# MJ808_clone_-_all_driver_-_prod_-_23mm.net
KiCad netlist of a schematic drawn in EAGLE
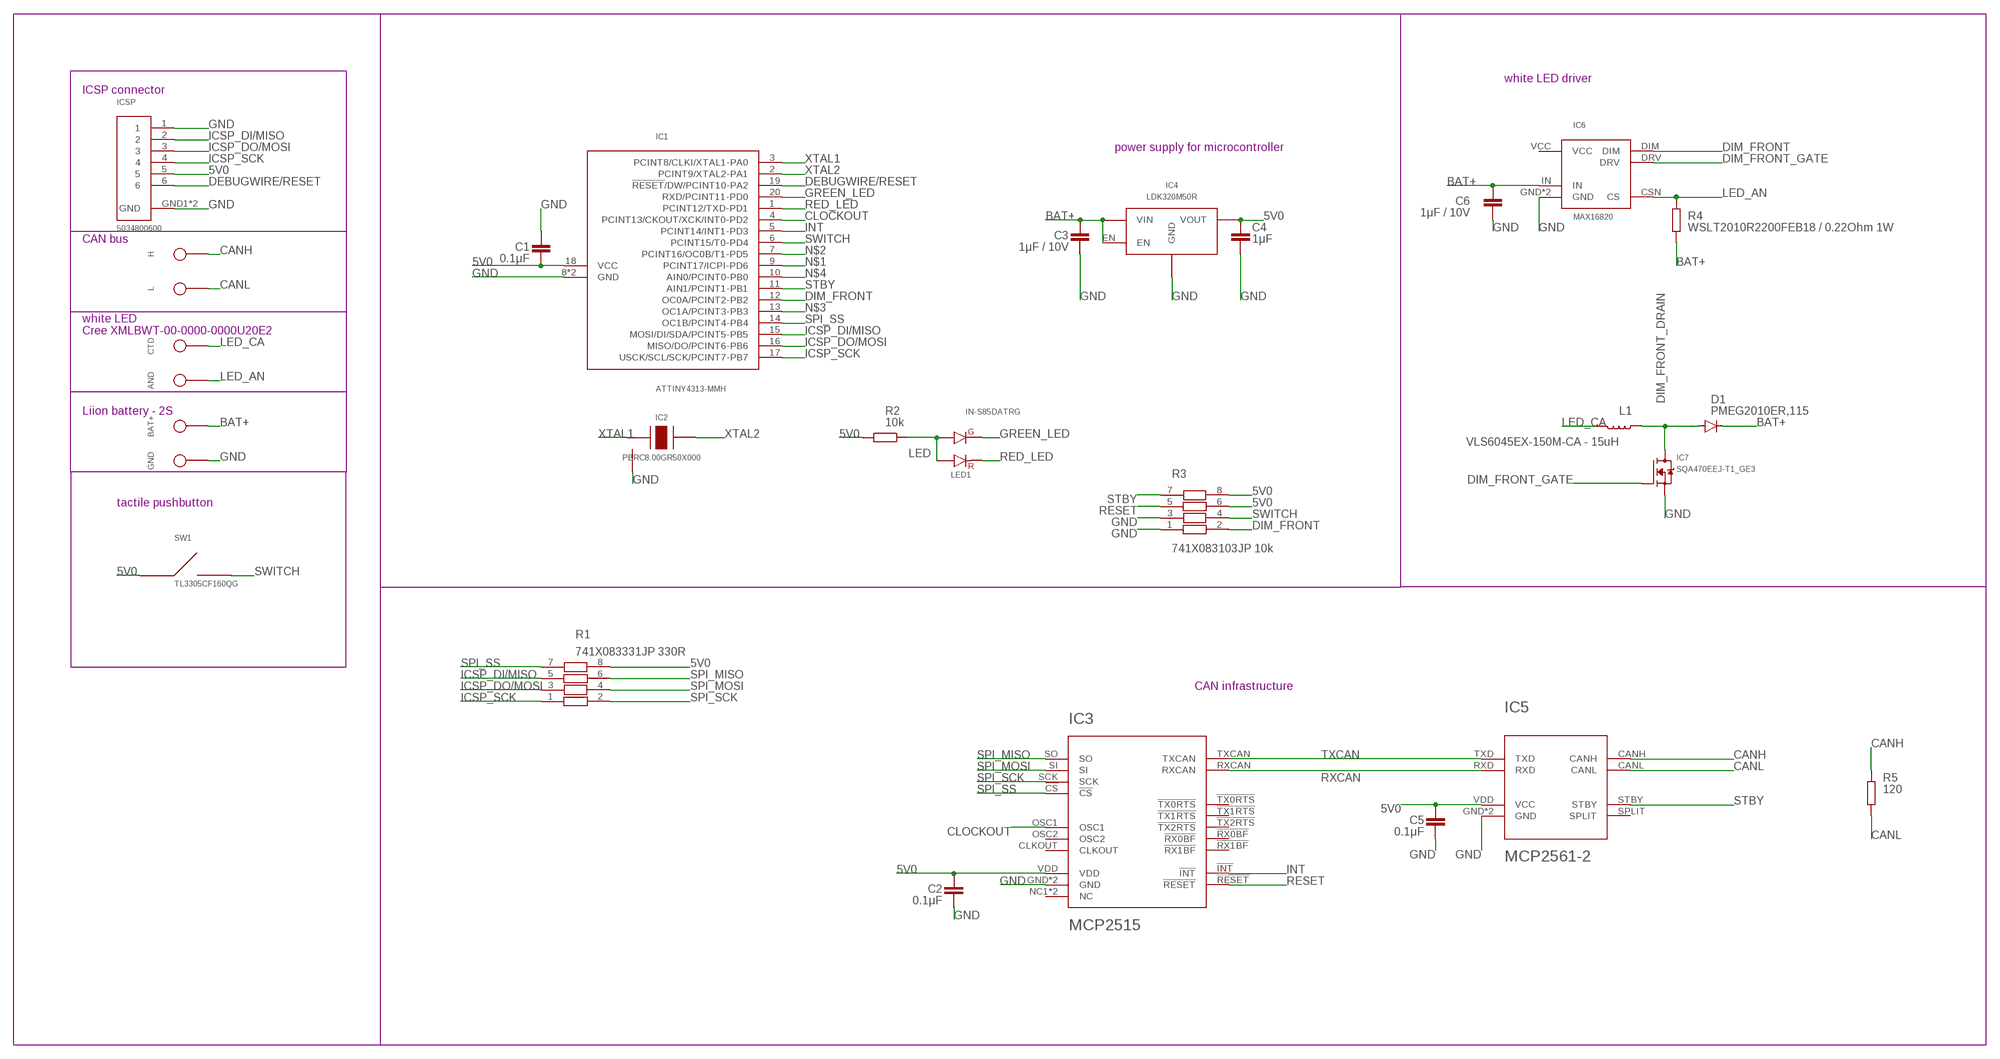
[diagram p0: schematic, sheet 1]

(export (version "E")
  (design (tool "Eeschema 10.0.6"))
  (components
    (comp (ref "AND")
      (value "LED anode")
      (footprint "eagle-import:TH-1.2MM")
      (libsource (lib "eagle-import") (part "TPTH-1.2MM"))
    )
    (comp (ref "BAT+")
      (value "LiIon + Terminal")
      (footprint "eagle-import:TH-1.2MM")
      (libsource (lib "eagle-import") (part "TPTH-1.2MM"))
    )
    (comp (ref "C1")
      (value "0.1μF")
      (footprint "eagle-import:C0402")
      (libsource (lib "eagle-import") (part "C-EUC0402"))
    )
    (comp (ref "C2")
      (value "0.1μF")
      (footprint "eagle-import:C0402")
      (libsource (lib "eagle-import") (part "C-EUC0402"))
    )
    (comp (ref "C3")
      (value "1μF / 10V")
      (footprint "eagle-import:C0402")
      (libsource (lib "eagle-import") (part "C-EUC0402"))
    )
    (comp (ref "C4")
      (value "1μF")
      (footprint "eagle-import:C0402")
      (libsource (lib "eagle-import") (part "C-EUC0402"))
    )
    (comp (ref "C5")
      (value "0.1μF")
      (footprint "eagle-import:C0402")
      (libsource (lib "eagle-import") (part "C-EUC0402"))
    )
    (comp (ref "C6")
      (value "1μF / 10V")
      (footprint "eagle-import:C0402")
      (libsource (lib "eagle-import") (part "C-EUC0402"))
    )
    (comp (ref "CTD")
      (value "LED cathode")
      (footprint "eagle-import:TH-1.2MM")
      (libsource (lib "eagle-import") (part "TPTH-1.2MM"))
    )
    (comp (ref "D1")
      (value "PMEG2010ER,115")
      (footprint "eagle-import:SOD123")
      (libsource (lib "eagle-import") (part "DIODE-SOD123"))
    )
    (comp (ref "GND")
      (value "LiIon - Terminal")
      (footprint "eagle-import:TH-1.2MM")
      (libsource (lib "eagle-import") (part "TPTH-1.2MM"))
    )
    (comp (ref "H")
      (value "CAN high")
      (footprint "eagle-import:TH-1.2MM")
      (libsource (lib "eagle-import") (part "TPTH-1.2MM"))
    )
    (comp (ref "IC1")
      (value "ATTINY4313-MMH")
      (footprint "eagle-import:VQFN-20")
      (fields (field (name "SPICEPREFIX") "X"))
      (libsource (lib "eagle-import") (part "ATTINY4313VQFN-20"))
    )
    (comp (ref "IC2")
      (value "PBRC8.00GR50X000")
      (footprint "eagle-import:SMT")
      (libsource (lib "eagle-import") (part "PRQV"))
    )
    (comp (ref "IC3")
      (value "MCP2515")
      (footprint "eagle-import:QFN20")
      (libsource (lib "eagle-import") (part "MCP2515-I-ML"))
    )
    (comp (ref "IC4")
      (value "LDK320M50R")
      (footprint "eagle-import:SOT-23-5L")
      (libsource (lib "eagle-import") (part "LDK320SOT-23-5L"))
    )
    (comp (ref "IC5")
      (value "MCP2561-2")
      (footprint "eagle-import:DFN10")
      (libsource (lib "eagle-import") (part "MCP2561-2"))
    )
    (comp (ref "IC6")
      (value "MAX16820")
      (footprint "eagle-import:TDFN-6-EP")
      (libsource (lib "eagle-import") (part "MAX16820"))
    )
    (comp (ref "IC7")
      (value "SQA470EEJ-T1_GE3")
      (footprint "eagle-import:SC-70-6")
      (libsource (lib "eagle-import") (part "SIA456DJ"))
    )
    (comp (ref "ICSP")
      (value "5034800600")
      (footprint "eagle-import:SMT")
      (libsource (lib "eagle-import") (part "5034800600"))
    )
    (comp (ref "L")
      (value "CAN low")
      (footprint "eagle-import:TH-1.2MM")
      (libsource (lib "eagle-import") (part "TPTH-1.2MM"))
    )
    (comp (ref "L1")
      (value "VLS6045EX-150M-CA - 15uH")
      (footprint "eagle-import:SRN6045")
      (libsource (lib "eagle-import") (part "INDUCTOR-SRN6045-33UH"))
    )
    (comp (ref "LED1")
      (value "IN-S85DATRG")
      (footprint "eagle-import:SMD")
      (libsource (lib "eagle-import") (part "APHBM2012LSURKZGKC"))
    )
    (comp (ref "R1")
      (value "741X083331JP 330R")
      (footprint "eagle-import:0402-4R")
      (libsource (lib "eagle-import") (part "741X083331JP"))
    )
    (comp (ref "R2")
      (value "10k")
      (footprint "eagle-import:R0402")
      (libsource (lib "eagle-import") (part "R-EU_R0402"))
    )
    (comp (ref "R3")
      (value "741X083103JP 10k")
      (footprint "eagle-import:0402-4R")
      (libsource (lib "eagle-import") (part "741X083331JP"))
    )
    (comp (ref "R4")
      (value "WSLT2010R2200FEB18 / 0.22Ohm 1W")
      (footprint "eagle-import:R2010")
      (libsource (lib "eagle-import") (part "R-EU_R2010"))
    )
    (comp (ref "R5")
      (value "120")
      (footprint "eagle-import:R0805")
      (libsource (lib "eagle-import") (part "R-EU_R0805"))
    )
    (comp (ref "SW1")
      (value "TL3305CF160QG")
      (footprint "eagle-import:SMD")
      (libsource (lib "eagle-import") (part "TL3305-844809"))
    )
  )
  (nets
    (net (code "1") (name "/5V0") (class "Default")
      (node (ref "C1") (pin "1") (pinfunction "1_1") (pintype "passive"))
      (node (ref "C2") (pin "1") (pinfunction "1_1") (pintype "passive"))
      (node (ref "C4") (pin "2") (pinfunction "2_2") (pintype "passive"))
      (node (ref "C5") (pin "1") (pinfunction "1_1") (pintype "passive"))
      (node (ref "IC1") (pin "18") (pinfunction "VCC_18") (pintype "bidirectional"))
      (node (ref "IC3") (pin "VDD") (pinfunction "VDD_VDD") (pintype "power_in"))
      (node (ref "IC4") (pin "OUT") (pinfunction "VOUT_OUT") (pintype "bidirectional"))
      (node (ref "IC5") (pin "VDD") (pinfunction "VCC_VDD") (pintype "power_in"))
      (node (ref "ICSP") (pin "5") (pinfunction "5_5") (pintype "bidirectional"))
      (node (ref "R1") (pin "8") (pinfunction "8_8") (pintype "bidirectional"))
      (node (ref "R2") (pin "2") (pinfunction "2_2") (pintype "passive"))
      (node (ref "R3") (pin "6") (pinfunction "6_6") (pintype "bidirectional"))
      (node (ref "R3") (pin "8") (pinfunction "8_8") (pintype "bidirectional"))
      (node (ref "SW1") (pin "1") (pinfunction "P$1_1") (pintype "bidirectional"))
      (node (ref "SW1") (pin "2") (pinfunction "P$1_2") (pintype "bidirectional"))
    )
    (net (code "2") (name "/BAT+") (class "Default")
      (node (ref "BAT+") (pin "TP$1") (pinfunction "TP$1_TP$1") (pintype "bidirectional"))
      (node (ref "C3") (pin "1") (pinfunction "1_1") (pintype "passive"))
      (node (ref "C6") (pin "1") (pinfunction "1_1") (pintype "passive"))
      (node (ref "D1") (pin "C") (pinfunction "C_C") (pintype "passive"))
      (node (ref "IC4") (pin "EN") (pinfunction "EN_EN") (pintype "bidirectional"))
      (node (ref "IC4") (pin "IN") (pinfunction "VIN_IN") (pintype "bidirectional"))
      (node (ref "IC6") (pin "IN") (pinfunction "IN_IN") (pintype "power_in"))
      (node (ref "R4") (pin "2") (pinfunction "2_2") (pintype "passive"))
    )
    (net (code "3") (name "/CANH") (class "Default")
      (node (ref "H") (pin "TP$1") (pinfunction "TP$1_TP$1") (pintype "bidirectional"))
      (node (ref "IC5") (pin "CANH") (pinfunction "CANH_CANH") (pintype "bidirectional"))
      (node (ref "R5") (pin "2") (pinfunction "2_2") (pintype "passive"))
    )
    (net (code "4") (name "/CANL") (class "Default")
      (node (ref "IC5") (pin "CANL") (pinfunction "CANL_CANL") (pintype "bidirectional"))
      (node (ref "L") (pin "TP$1") (pinfunction "TP$1_TP$1") (pintype "bidirectional"))
      (node (ref "R5") (pin "1") (pinfunction "1_1") (pintype "passive"))
    )
    (net (code "5") (name "/CLOCKOUT") (class "Default")
      (node (ref "IC1") (pin "4") (pinfunction "PCINT13/CKOUT/XCK/INT0-PD2_4") (pintype "bidirectional"))
      (node (ref "IC3") (pin "OSC1") (pinfunction "OSC1_OSC1") (pintype "bidirectional"))
    )
    (net (code "6") (name "/DEBUGWIRE{slash}RESET") (class "Default")
      (node (ref "IC1") (pin "19") (pinfunction "~{RESET}/DW/PCINT10-PA2_19") (pintype "bidirectional"))
      (node (ref "ICSP") (pin "6") (pinfunction "6_6") (pintype "bidirectional"))
    )
    (net (code "7") (name "/DIM_FRONT") (class "Default")
      (node (ref "IC1") (pin "12") (pinfunction "OC0A/PCINT2-PB2_12") (pintype "bidirectional"))
      (node (ref "IC6") (pin "DIM") (pinfunction "DIM_DIM") (pintype "bidirectional"))
      (node (ref "R3") (pin "2") (pinfunction "2_2") (pintype "bidirectional"))
    )
    (net (code "8") (name "/DIM_FRONT_DRAIN") (class "Default")
      (node (ref "D1") (pin "A") (pinfunction "A_A") (pintype "passive"))
      (node (ref "IC7") (pin "1D") (pinfunction "D_1D") (pintype "passive"))
      (node (ref "IC7") (pin "2D") (pinfunction "D_2D") (pintype "passive"))
      (node (ref "IC7") (pin "5D") (pinfunction "D_5D") (pintype "passive"))
      (node (ref "IC7") (pin "6D") (pinfunction "D_6D") (pintype "passive"))
      (node (ref "IC7") (pin "D") (pinfunction "D_D") (pintype "passive"))
      (node (ref "L1") (pin "1") (pinfunction "1_1") (pintype "passive"))
    )
    (net (code "9") (name "/DIM_FRONT_GATE") (class "Default")
      (node (ref "IC6") (pin "DRV") (pinfunction "DRV_DRV") (pintype "bidirectional"))
      (node (ref "IC7") (pin "3G") (pinfunction "G_3G") (pintype "passive"))
    )
    (net (code "10") (name "/GND") (class "Default")
      (node (ref "C1") (pin "2") (pinfunction "2_2") (pintype "passive"))
      (node (ref "C2") (pin "2") (pinfunction "2_2") (pintype "passive"))
      (node (ref "C3") (pin "2") (pinfunction "2_2") (pintype "passive"))
      (node (ref "C4") (pin "1") (pinfunction "1_1") (pintype "passive"))
      (node (ref "C5") (pin "2") (pinfunction "2_2") (pintype "passive"))
      (node (ref "C6") (pin "2") (pinfunction "2_2") (pintype "passive"))
      (node (ref "GND") (pin "TP$1") (pinfunction "TP$1_TP$1") (pintype "bidirectional"))
      (node (ref "IC1") (pin "8") (pinfunction "GND_8") (pintype "bidirectional"))
      (node (ref "IC1") (pin "GND") (pinfunction "GND_GND") (pintype "bidirectional"))
      (node (ref "IC2") (pin "GND") (pinfunction "GND_GND") (pintype "bidirectional"))
      (node (ref "IC3") (pin "GND") (pinfunction "GND_GND") (pintype "power_in"))
      (node (ref "IC3") (pin "GND6") (pinfunction "GND_GND6") (pintype "power_in"))
      (node (ref "IC4") (pin "GND") (pinfunction "GND_GND") (pintype "bidirectional"))
      (node (ref "IC5") (pin "GND") (pinfunction "GND_GND") (pintype "power_in"))
      (node (ref "IC5") (pin "VSS") (pinfunction "GND_VSS") (pintype "power_in"))
      (node (ref "IC6") (pin "GND") (pinfunction "GND_GND") (pintype "power_in"))
      (node (ref "IC6") (pin "GND1") (pinfunction "GND_GND1") (pintype "power_in"))
      (node (ref "IC7") (pin "4S") (pinfunction "S_4S") (pintype "passive"))
      (node (ref "IC7") (pin "S") (pinfunction "S_S") (pintype "passive"))
      (node (ref "ICSP") (pin "1") (pinfunction "1_1") (pintype "bidirectional"))
      (node (ref "ICSP") (pin "GND1") (pinfunction "GND_GND1") (pintype "bidirectional"))
      (node (ref "ICSP") (pin "GND2") (pinfunction "GND_GND2") (pintype "bidirectional"))
      (node (ref "R3") (pin "1") (pinfunction "1_1") (pintype "bidirectional"))
      (node (ref "R3") (pin "3") (pinfunction "3_3") (pintype "bidirectional"))
    )
    (net (code "11") (name "/GREEN_LED") (class "Default")
      (node (ref "IC1") (pin "20") (pinfunction "RXD/PCINT11-PD0_20") (pintype "bidirectional"))
      (node (ref "LED1") (pin "3") (pinfunction "3_3") (pintype "bidirectional"))
    )
    (net (code "12") (name "/ICSP_DI{slash}MISO") (class "Default")
      (node (ref "IC1") (pin "15") (pinfunction "MOSI/DI/SDA/PCINT5-PB5_15") (pintype "bidirectional"))
      (node (ref "ICSP") (pin "2") (pinfunction "2_2") (pintype "bidirectional"))
      (node (ref "R1") (pin "5") (pinfunction "5_5") (pintype "bidirectional"))
    )
    (net (code "13") (name "/ICSP_DO{slash}MOSI") (class "Default")
      (node (ref "IC1") (pin "16") (pinfunction "MISO/DO/PCINT6-PB6_16") (pintype "bidirectional"))
      (node (ref "ICSP") (pin "3") (pinfunction "3_3") (pintype "bidirectional"))
      (node (ref "R1") (pin "3") (pinfunction "3_3") (pintype "bidirectional"))
    )
    (net (code "14") (name "/ICSP_SCK") (class "Default")
      (node (ref "IC1") (pin "17") (pinfunction "USCK/SCL/SCK/PCINT7-PB7_17") (pintype "bidirectional"))
      (node (ref "ICSP") (pin "4") (pinfunction "4_4") (pintype "bidirectional"))
      (node (ref "R1") (pin "1") (pinfunction "1_1") (pintype "bidirectional"))
    )
    (net (code "15") (name "/INT") (class "Default")
      (node (ref "IC1") (pin "5") (pinfunction "PCINT14/INT1-PD3_5") (pintype "bidirectional"))
      (node (ref "IC3") (pin "!INT!") (pinfunction "~{INT}_!INT!") (pintype "bidirectional"))
    )
    (net (code "16") (name "/LED") (class "Default")
      (node (ref "LED1") (pin "1") (pinfunction "1_1") (pintype "bidirectional"))
      (node (ref "LED1") (pin "4") (pinfunction "4_4") (pintype "bidirectional"))
      (node (ref "R2") (pin "1") (pinfunction "1_1") (pintype "passive"))
    )
    (net (code "17") (name "/LED_AN") (class "Default")
      (node (ref "AND") (pin "TP$1") (pinfunction "TP$1_TP$1") (pintype "bidirectional"))
      (node (ref "IC6") (pin "CSN") (pinfunction "CS_CSN") (pintype "bidirectional"))
      (node (ref "R4") (pin "1") (pinfunction "1_1") (pintype "passive"))
    )
    (net (code "18") (name "/LED_CA") (class "Default")
      (node (ref "CTD") (pin "TP$1") (pinfunction "TP$1_TP$1") (pintype "bidirectional"))
      (node (ref "L1") (pin "2") (pinfunction "2_2") (pintype "passive"))
    )
    (net (code "19") (name "/N$1") (class "Default")
      (node (ref "IC1") (pin "9") (pinfunction "PCINT17/ICPI-PD6_9") (pintype "bidirectional"))
    )
    (net (code "20") (name "/N$2") (class "Default")
      (node (ref "IC1") (pin "7") (pinfunction "PCINT16/OC0B/T1-PD5_7") (pintype "bidirectional"))
    )
    (net (code "21") (name "/N$3") (class "Default")
      (node (ref "IC1") (pin "13") (pinfunction "OC1A/PCINT3-PB3_13") (pintype "bidirectional"))
    )
    (net (code "22") (name "/N$4") (class "Default")
      (node (ref "IC1") (pin "10") (pinfunction "AIN0/PCINT0-PB0_10") (pintype "bidirectional"))
    )
    (net (code "23") (name "/RED_LED") (class "Default")
      (node (ref "IC1") (pin "1") (pinfunction "PCINT12/TXD-PD1_1") (pintype "bidirectional"))
      (node (ref "LED1") (pin "2") (pinfunction "2_2") (pintype "bidirectional"))
    )
    (net (code "24") (name "/RESET") (class "Default")
      (node (ref "IC3") (pin "!RESET!") (pinfunction "~{RESET}_!RESET!") (pintype "bidirectional"))
      (node (ref "R3") (pin "5") (pinfunction "5_5") (pintype "bidirectional"))
    )
    (net (code "25") (name "/RXCAN") (class "Default")
      (node (ref "IC3") (pin "RXCAN") (pinfunction "RXCAN_RXCAN") (pintype "input"))
      (node (ref "IC5") (pin "RXD") (pinfunction "RXD_RXD") (pintype "output"))
    )
    (net (code "26") (name "/SPI_MISO") (class "Default")
      (node (ref "IC3") (pin "SO") (pinfunction "SO_SO") (pintype "output"))
      (node (ref "R1") (pin "6") (pinfunction "6_6") (pintype "bidirectional"))
    )
    (net (code "27") (name "/SPI_MOSI") (class "Default")
      (node (ref "IC3") (pin "SI") (pinfunction "SI_SI") (pintype "input"))
      (node (ref "R1") (pin "4") (pinfunction "4_4") (pintype "bidirectional"))
    )
    (net (code "28") (name "/SPI_SCK") (class "Default")
      (node (ref "IC3") (pin "SCK") (pinfunction "SCK_SCK") (pintype "bidirectional"))
      (node (ref "R1") (pin "2") (pinfunction "2_2") (pintype "bidirectional"))
    )
    (net (code "29") (name "/SPI_SS") (class "Default")
      (node (ref "IC1") (pin "14") (pinfunction "OC1B/PCINT4-PB4_14") (pintype "bidirectional"))
      (node (ref "IC3") (pin "!CS!") (pinfunction "~{CS}_!CS!") (pintype "bidirectional"))
      (node (ref "R1") (pin "7") (pinfunction "7_7") (pintype "bidirectional"))
    )
    (net (code "30") (name "/STBY") (class "Default")
      (node (ref "IC1") (pin "11") (pinfunction "AIN1/PCINT1-PB1_11") (pintype "bidirectional"))
      (node (ref "IC5") (pin "STBY") (pinfunction "STBY_STBY") (pintype "bidirectional"))
      (node (ref "R3") (pin "7") (pinfunction "7_7") (pintype "bidirectional"))
    )
    (net (code "31") (name "/SWITCH") (class "Default")
      (node (ref "IC1") (pin "6") (pinfunction "PCINT15/T0-PD4_6") (pintype "bidirectional"))
      (node (ref "R3") (pin "4") (pinfunction "4_4") (pintype "bidirectional"))
      (node (ref "SW1") (pin "3") (pinfunction "P$2_3") (pintype "bidirectional"))
      (node (ref "SW1") (pin "4") (pinfunction "P$2_4") (pintype "bidirectional"))
    )
    (net (code "32") (name "/TXCAN") (class "Default")
      (node (ref "IC3") (pin "TXCAN") (pinfunction "TXCAN_TXCAN") (pintype "output"))
      (node (ref "IC5") (pin "TXD") (pinfunction "TXD_TXD") (pintype "input"))
    )
    (net (code "33") (name "/VCC") (class "Default")
      (node (ref "IC6") (pin "VCC") (pinfunction "VCC_VCC") (pintype "power_in"))
    )
    (net (code "34") (name "/XTAL1") (class "Default")
      (node (ref "IC1") (pin "3") (pinfunction "PCINT8/CLKI/XTAL1-PA0_3") (pintype "bidirectional"))
      (node (ref "IC2") (pin "XTAL1") (pinfunction "XTAL1_XTAL1") (pintype "bidirectional"))
    )
    (net (code "35") (name "/XTAL2") (class "Default")
      (node (ref "IC1") (pin "2") (pinfunction "PCINT9/XTAL2-PA1_2") (pintype "bidirectional"))
      (node (ref "IC2") (pin "XTAL2") (pinfunction "XTAL2_XTAL2") (pintype "bidirectional"))
    )
    (net (code "36") (name "unconnected-(IC3-NC-PadNC1)") (class "Default")
      (node (ref "IC3") (pin "NC1") (pinfunction "NC_NC1") (pintype "no_connect"))
    )
    (net (code "37") (name "unconnected-(IC3-NC-PadNC2)") (class "Default")
      (node (ref "IC3") (pin "NC2") (pinfunction "NC_NC2") (pintype "no_connect"))
    )
    (net (code "38") (name "unconnected-(IC3-PadCLKOUT)") (class "Default")
      (node (ref "IC3") (pin "CLKOUT") (pinfunction "CLKOUT_CLKOUT") (pintype "bidirectional"))
    )
    (net (code "39") (name "unconnected-(IC3-PadOSC2)") (class "Default")
      (node (ref "IC3") (pin "OSC2") (pinfunction "OSC2_OSC2") (pintype "bidirectional"))
    )
    (net (code "40") (name "unconnected-(IC3-~{RX0BF}-Pad!RX0BF!)") (class "Default")
      (node (ref "IC3") (pin "!RX0BF!") (pinfunction "~{RX0BF}_!RX0BF!") (pintype "bidirectional"))
    )
    (net (code "41") (name "unconnected-(IC3-~{RX1BF}-Pad!RX1BF!)") (class "Default")
      (node (ref "IC3") (pin "!RX1BF!") (pinfunction "~{RX1BF}_!RX1BF!") (pintype "bidirectional"))
    )
    (net (code "42") (name "unconnected-(IC3-~{TX0RTS}-Pad!TX0RTS!)") (class "Default")
      (node (ref "IC3") (pin "!TX0RTS!") (pinfunction "~{TX0RTS}_!TX0RTS!") (pintype "bidirectional"))
    )
    (net (code "43") (name "unconnected-(IC3-~{TX1RTS}-Pad!TX1RTS!)") (class "Default")
      (node (ref "IC3") (pin "!TX1RTS!") (pinfunction "~{TX1RTS}_!TX1RTS!") (pintype "bidirectional"))
    )
    (net (code "44") (name "unconnected-(IC3-~{TX2RTS}-Pad!TX2RTS!)") (class "Default")
      (node (ref "IC3") (pin "!TX2RTS!") (pinfunction "~{TX2RTS}_!TX2RTS!") (pintype "bidirectional"))
    )
    (net (code "45") (name "unconnected-(IC5-PadSPLIT)") (class "Default")
      (node (ref "IC5") (pin "SPLIT") (pinfunction "SPLIT_SPLIT") (pintype "bidirectional"))
    )
  )
)
